# Audio_Docking_Station.net
KiCad netlist of a schematic drawn in Altium Designer
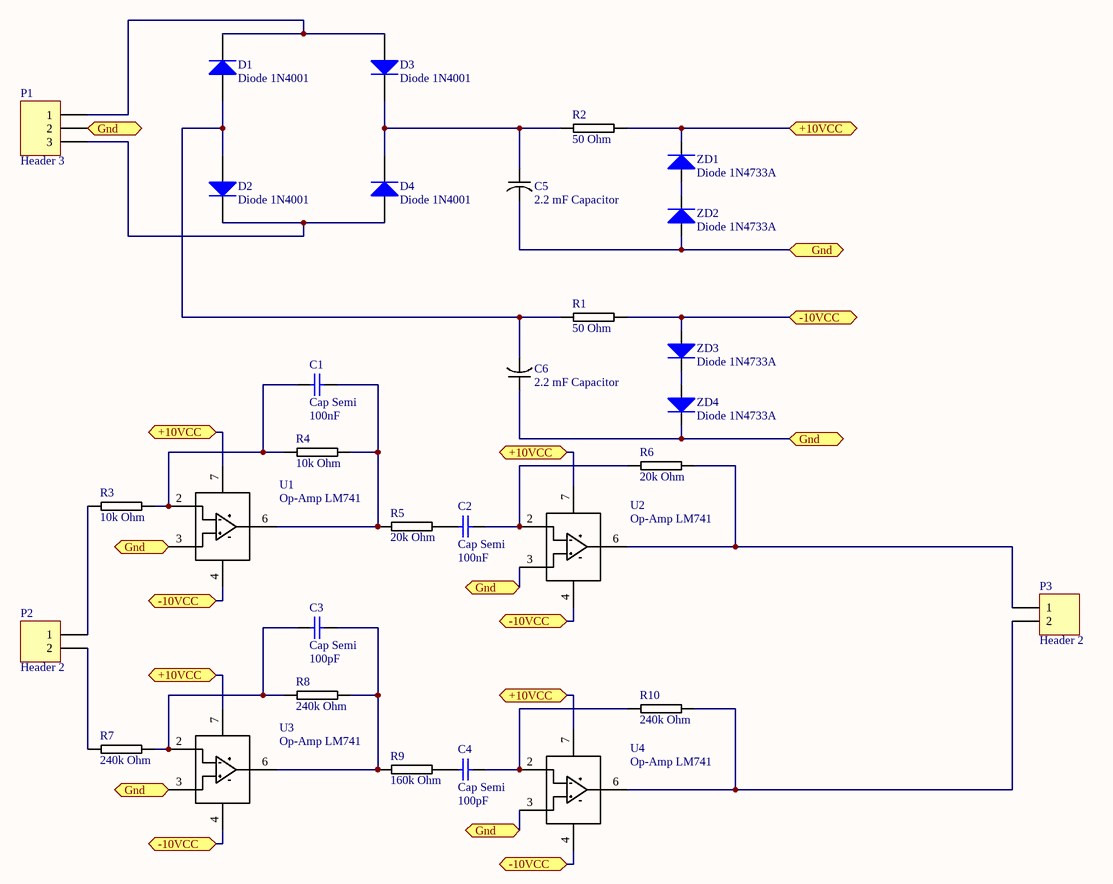
[diagram p0: Audio_Docking_Station.SchDoc]

(export (version "E")
  (design (tool "Eeschema 10.0.6"))
  (components
    (comp (ref "C1")
      (value "Cap Semi")
      (footprint "0402")
      (description "Capacitor (Semiconductor SIM Model)")
      (fields (field (name "ALTIUM_VALUE") "100nF") (field (name "PUBLISHER") "Altium Limited"))
      (libsource (lib "Miscellaneous Devices") (part "Cap Semi"))
    )
    (comp (ref "C2")
      (value "Cap Semi")
      (footprint "0402")
      (description "Capacitor (Semiconductor SIM Model)")
      (fields (field (name "ALTIUM_VALUE") "100nF") (field (name "PUBLISHER") "Altium Limited"))
      (libsource (lib "Miscellaneous Devices") (part "Cap Semi"))
    )
    (comp (ref "C3")
      (value "Cap Semi")
      (footprint "0402")
      (description "Capacitor (Semiconductor SIM Model)")
      (fields (field (name "ALTIUM_VALUE") "100pF") (field (name "PUBLISHER") "Altium Limited"))
      (libsource (lib "Miscellaneous Devices") (part "Cap Semi"))
    )
    (comp (ref "C4")
      (value "Cap Semi")
      (footprint "0402")
      (description "Capacitor (Semiconductor SIM Model)")
      (fields (field (name "ALTIUM_VALUE") "100pF") (field (name "PUBLISHER") "Altium Limited"))
      (libsource (lib "Miscellaneous Devices") (part "Cap Semi"))
    )
    (comp (ref "C5")
      (value "2.2 mF Capacitor")
      (footprint "2.2mF Capacitor")
      (libsource (lib "PCB_Schematics") (part "2.2 mF Capacitor"))
    )
    (comp (ref "C6")
      (value "2.2 mF Capacitor")
      (footprint "2.2mF Capacitor")
      (libsource (lib "PCB_Schematics") (part "2.2 mF Capacitor"))
    )
    (comp (ref "D1")
      (value "Diode 1N4001")
      (footprint "DO-41")
      (description "1 Amp General Purpose Rectifier")
      (fields (field (name "PUBLISHER") "Altium Limited"))
      (libsource (lib "Miscellaneous Devices") (part "Diode 1N4001"))
    )
    (comp (ref "D2")
      (value "Diode 1N4001")
      (footprint "DO-41")
      (description "1 Amp General Purpose Rectifier")
      (fields (field (name "PUBLISHER") "Altium Limited"))
      (libsource (lib "Miscellaneous Devices") (part "Diode 1N4001"))
    )
    (comp (ref "D3")
      (value "Diode 1N4001")
      (footprint "DO-41")
      (description "1 Amp General Purpose Rectifier")
      (fields (field (name "PUBLISHER") "Altium Limited"))
      (libsource (lib "Miscellaneous Devices") (part "Diode 1N4001"))
    )
    (comp (ref "D4")
      (value "Diode 1N4001")
      (footprint "DO-41")
      (description "1 Amp General Purpose Rectifier")
      (fields (field (name "PUBLISHER") "Altium Limited"))
      (libsource (lib "Miscellaneous Devices") (part "Diode 1N4001"))
    )
    (comp (ref "P1")
      (value "Header 3")
      (footprint "HDR1X3")
      (description "Header, 3-Pin")
      (fields (field (name "PUBLISHER") "Altium Limited"))
      (libsource (lib "Miscellaneous Connectors") (part "Header 3"))
    )
    (comp (ref "P2")
      (value "Header 2")
      (footprint "HDR1X2")
      (description "Header, 2-Pin")
      (fields (field (name "PUBLISHER") "Altium Limited"))
      (libsource (lib "Miscellaneous Connectors") (part "Header 2"))
    )
    (comp (ref "P3")
      (value "Header 2")
      (footprint "HDR1X2")
      (description "Header, 2-Pin")
      (fields (field (name "PUBLISHER") "Altium Limited"))
      (libsource (lib "") (part "Header 2_1"))
    )
    (comp (ref "R1")
      (value "50 Ohm")
      (footprint "0603R-TBD")
      (description "RESISTOR 0603")
      (libsource (lib "vh_altium_library") (part "0603R-TBD"))
    )
    (comp (ref "R2")
      (value "50 Ohm")
      (footprint "0603R-TBD")
      (description "RESISTOR 0603 VALUE TO BE DETERMINED")
      (libsource (lib "vh_altium_library") (part "0603R-TBD"))
    )
    (comp (ref "R3")
      (value "10k Ohm")
      (footprint "0402R-TBD")
      (libsource (lib "vh_altium_library") (part "0402R-TBD"))
    )
    (comp (ref "R4")
      (value "10k Ohm")
      (footprint "0402R-TBD")
      (libsource (lib "vh_altium_library") (part "0402R-TBD"))
    )
    (comp (ref "R5")
      (value "20k Ohm")
      (footprint "0603R-TBD")
      (description "RESISTOR 0603")
      (libsource (lib "vh_altium_library") (part "0603R-TBD"))
    )
    (comp (ref "R6")
      (value "20k Ohm")
      (footprint "0603R-TBD")
      (description "RESISTOR 0603")
      (libsource (lib "vh_altium_library") (part "0603R-TBD"))
    )
    (comp (ref "R7")
      (value "240k Ohm")
      (footprint "0603R-TBD")
      (description "RESISTOR 0603")
      (libsource (lib "vh_altium_library") (part "0603R-TBD"))
    )
    (comp (ref "R8")
      (value "240k Ohm")
      (footprint "0603R-TBD")
      (description "RESISTOR 0603")
      (libsource (lib "vh_altium_library") (part "0603R-TBD"))
    )
    (comp (ref "R9")
      (value "160k Ohm")
      (footprint "0603R-TBD")
      (description "RESISTOR 0603")
      (libsource (lib "vh_altium_library") (part "0603R-TBD"))
    )
    (comp (ref "R10")
      (value "240k Ohm")
      (footprint "0603R-TBD")
      (description "RESISTOR 0603")
      (libsource (lib "vh_altium_library") (part "0603R-TBD"))
    )
    (comp (ref "U1")
      (value "Op-Amp LM741")
      (footprint "8-DIP")
      (libsource (lib "PCB_Schematics") (part "Op-Amp LM741"))
    )
    (comp (ref "U2")
      (value "Op-Amp LM741")
      (footprint "8-DIP")
      (libsource (lib "PCB_Schematics") (part "Op-Amp LM741"))
    )
    (comp (ref "U3")
      (value "Op-Amp LM741")
      (footprint "8-DIP")
      (libsource (lib "PCB_Schematics") (part "Op-Amp LM741"))
    )
    (comp (ref "U4")
      (value "Op-Amp LM741")
      (footprint "8-DIP")
      (libsource (lib "PCB_Schematics") (part "Op-Amp LM741"))
    )
    (comp (ref "ZD1")
      (value "Diode 1N4733A")
      (footprint "DO-41G")
      (libsource (lib "PCB_Schematics") (part "Diode 1N4733A"))
    )
    (comp (ref "ZD2")
      (value "Diode 1N4733A")
      (footprint "DO-41G")
      (libsource (lib "PCB_Schematics") (part "Diode 1N4733A"))
    )
    (comp (ref "ZD3")
      (value "Diode 1N4733A")
      (footprint "DO-41G")
      (libsource (lib "PCB_Schematics") (part "Diode 1N4733A"))
    )
    (comp (ref "ZD4")
      (value "Diode 1N4733A")
      (footprint "DO-41G")
      (libsource (lib "PCB_Schematics") (part "Diode 1N4733A"))
    )
  )
  (nets
    (net (code "1") (name "/+10VCC") (class "Default")
      (node (ref "R2") (pin "2") (pintype "passive"))
      (node (ref "U1") (pin "7") (pinfunction "7_7") (pintype "passive"))
      (node (ref "U2") (pin "7") (pinfunction "7_7") (pintype "passive"))
      (node (ref "U3") (pin "7") (pinfunction "7_7") (pintype "passive"))
      (node (ref "U4") (pin "7") (pinfunction "7_7") (pintype "passive"))
      (node (ref "ZD1") (pin "2") (pinfunction "2_2") (pintype "passive"))
    )
    (net (code "2") (name "/-10VCC") (class "Default")
      (node (ref "R1") (pin "2") (pintype "passive"))
      (node (ref "U1") (pin "4") (pinfunction "4_4") (pintype "passive"))
      (node (ref "U2") (pin "4") (pinfunction "4_4") (pintype "passive"))
      (node (ref "U3") (pin "4") (pinfunction "4_4") (pintype "passive"))
      (node (ref "U4") (pin "4") (pinfunction "4_4") (pintype "passive"))
      (node (ref "ZD3") (pin "1") (pinfunction "1_1") (pintype "passive"))
    )
    (net (code "3") (name "/Gnd") (class "Default")
      (node (ref "C5") (pin "1") (pinfunction "1_1") (pintype "passive"))
      (node (ref "C6") (pin "2") (pinfunction "2_2") (pintype "passive"))
      (node (ref "P1") (pin "2") (pinfunction "2_2") (pintype "passive"))
      (node (ref "U1") (pin "3") (pinfunction "3_3") (pintype "passive"))
      (node (ref "U2") (pin "3") (pinfunction "3_3") (pintype "passive"))
      (node (ref "U3") (pin "3") (pinfunction "3_3") (pintype "passive"))
      (node (ref "U4") (pin "3") (pinfunction "3_3") (pintype "passive"))
      (node (ref "ZD2") (pin "1") (pinfunction "1_1") (pintype "passive"))
      (node (ref "ZD4") (pin "2") (pinfunction "2_2") (pintype "passive"))
    )
    (net (code "4") (name "Net-(C1-Pad1)") (class "Default")
      (node (ref "C1") (pin "1") (pinfunction "1_1") (pintype "passive"))
      (node (ref "R3") (pin "2") (pintype "passive"))
      (node (ref "R4") (pin "1") (pintype "passive"))
      (node (ref "U1") (pin "2") (pinfunction "2_2") (pintype "passive"))
    )
    (net (code "5") (name "Net-(C1-Pad2)") (class "Default")
      (node (ref "C1") (pin "2") (pinfunction "2_2") (pintype "passive"))
      (node (ref "R4") (pin "2") (pintype "passive"))
      (node (ref "R5") (pin "1") (pintype "passive"))
      (node (ref "U1") (pin "6") (pinfunction "6_6") (pintype "passive"))
    )
    (net (code "6") (name "Net-(C2-Pad1)") (class "Default")
      (node (ref "C2") (pin "1") (pinfunction "1_1") (pintype "passive"))
      (node (ref "R5") (pin "2") (pintype "passive"))
    )
    (net (code "7") (name "Net-(C2-Pad2)") (class "Default")
      (node (ref "C2") (pin "2") (pinfunction "2_2") (pintype "passive"))
      (node (ref "R6") (pin "1") (pintype "passive"))
      (node (ref "U2") (pin "2") (pinfunction "2_2") (pintype "passive"))
    )
    (net (code "8") (name "Net-(C3-Pad1)") (class "Default")
      (node (ref "C3") (pin "1") (pinfunction "1_1") (pintype "passive"))
      (node (ref "R7") (pin "2") (pintype "passive"))
      (node (ref "R8") (pin "1") (pintype "passive"))
      (node (ref "U3") (pin "2") (pinfunction "2_2") (pintype "passive"))
    )
    (net (code "9") (name "Net-(C3-Pad2)") (class "Default")
      (node (ref "C3") (pin "2") (pinfunction "2_2") (pintype "passive"))
      (node (ref "R8") (pin "2") (pintype "passive"))
      (node (ref "R9") (pin "1") (pintype "passive"))
      (node (ref "U3") (pin "6") (pinfunction "6_6") (pintype "passive"))
    )
    (net (code "10") (name "Net-(C4-Pad1)") (class "Default")
      (node (ref "C4") (pin "1") (pinfunction "1_1") (pintype "passive"))
      (node (ref "R9") (pin "2") (pintype "passive"))
    )
    (net (code "11") (name "Net-(C4-Pad2)") (class "Default")
      (node (ref "C4") (pin "2") (pinfunction "2_2") (pintype "passive"))
      (node (ref "R10") (pin "1") (pintype "passive"))
      (node (ref "U4") (pin "2") (pinfunction "2_2") (pintype "passive"))
    )
    (net (code "12") (name "Net-(D1-A)") (class "Default")
      (node (ref "C6") (pin "1") (pinfunction "1_1") (pintype "passive"))
      (node (ref "D1") (pin "1") (pinfunction "A_1") (pintype "passive"))
      (node (ref "D2") (pin "1") (pinfunction "A_1") (pintype "passive"))
      (node (ref "R1") (pin "1") (pintype "passive"))
    )
    (net (code "13") (name "Net-(D1-K)") (class "Default")
      (node (ref "D1") (pin "2") (pinfunction "K_2") (pintype "passive"))
      (node (ref "D3") (pin "1") (pinfunction "A_1") (pintype "passive"))
      (node (ref "P1") (pin "1") (pinfunction "1_1") (pintype "passive"))
    )
    (net (code "14") (name "Net-(D2-K)") (class "Default")
      (node (ref "D2") (pin "2") (pinfunction "K_2") (pintype "passive"))
      (node (ref "D4") (pin "1") (pinfunction "A_1") (pintype "passive"))
      (node (ref "P1") (pin "3") (pinfunction "3_3") (pintype "passive"))
    )
    (net (code "15") (name "Net-(D3-K)") (class "Default")
      (node (ref "C5") (pin "2") (pinfunction "2_2") (pintype "passive"))
      (node (ref "D3") (pin "2") (pinfunction "K_2") (pintype "passive"))
      (node (ref "D4") (pin "2") (pinfunction "K_2") (pintype "passive"))
      (node (ref "R2") (pin "1") (pintype "passive"))
    )
    (net (code "16") (name "Net-(P2-Pad1)") (class "Default")
      (node (ref "P2") (pin "1") (pinfunction "1_1") (pintype "passive"))
      (node (ref "R3") (pin "1") (pintype "passive"))
    )
    (net (code "17") (name "Net-(P2-Pad2)") (class "Default")
      (node (ref "P2") (pin "2") (pinfunction "2_2") (pintype "passive"))
      (node (ref "R7") (pin "1") (pintype "passive"))
    )
    (net (code "18") (name "Net-(P3-Pad1)") (class "Default")
      (node (ref "P3") (pin "1") (pinfunction "1_1") (pintype "passive"))
      (node (ref "R6") (pin "2") (pintype "passive"))
      (node (ref "U2") (pin "6") (pinfunction "6_6") (pintype "passive"))
    )
    (net (code "19") (name "Net-(P3-Pad2)") (class "Default")
      (node (ref "P3") (pin "2") (pinfunction "2_2") (pintype "passive"))
      (node (ref "R10") (pin "2") (pintype "passive"))
      (node (ref "U4") (pin "6") (pinfunction "6_6") (pintype "passive"))
    )
    (net (code "20") (name "Net-(ZD1-Pad1)") (class "Default")
      (node (ref "ZD1") (pin "1") (pinfunction "1_1") (pintype "passive"))
      (node (ref "ZD2") (pin "2") (pinfunction "2_2") (pintype "passive"))
    )
    (net (code "21") (name "Net-(ZD3-Pad2)") (class "Default")
      (node (ref "ZD3") (pin "2") (pinfunction "2_2") (pintype "passive"))
      (node (ref "ZD4") (pin "1") (pinfunction "1_1") (pintype "passive"))
    )
  )
)
